# P16_Hi3531AV100_RGMII_I.net
KiCad netlist of a schematic drawn in Altium Designer
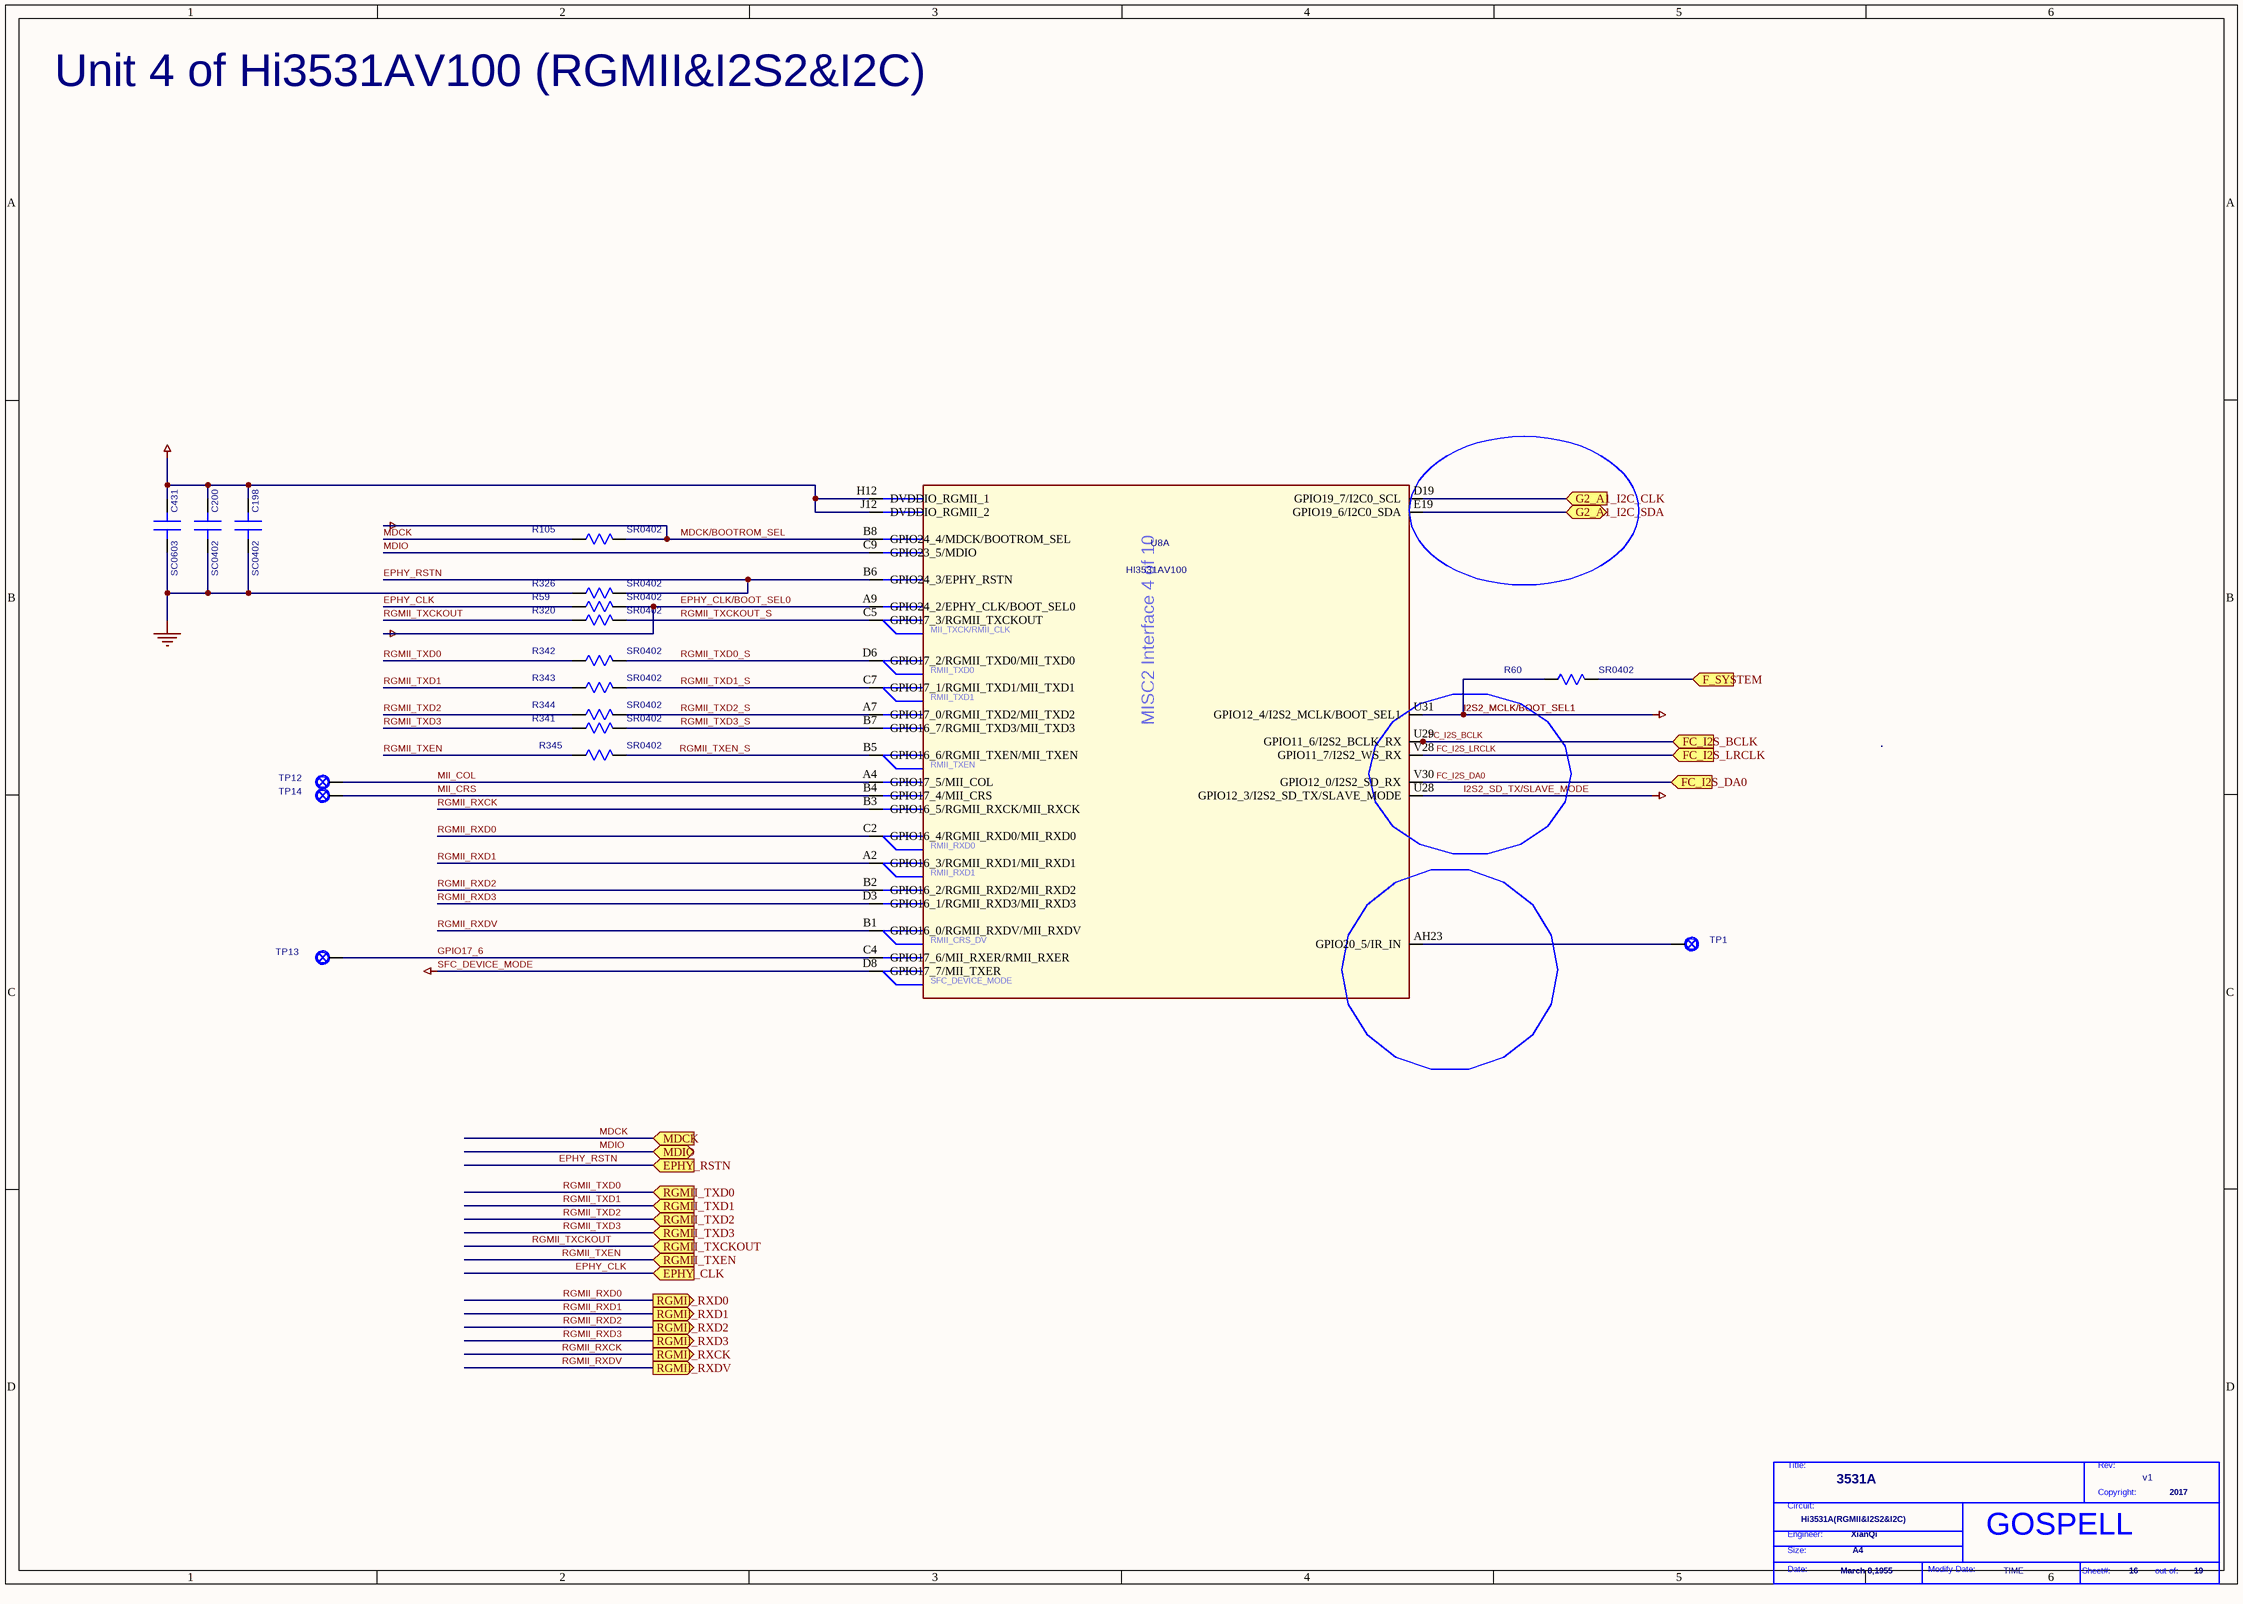
[diagram p0: P16 Hi3531AV100(RGMII&I.SchDoc]

(export (version "E")
  (design (tool "Eeschema 10.0.6"))
  (components
    (comp (ref "C198") (value "SC0402") (libsource (lib "*") (part "C_0_Dup2")))
    (comp (ref "C200") (value "SC0402") (libsource (lib "*") (part "C_0_Dup2")))
    (comp (ref "C431") (value "SC0603") (libsource (lib "*") (part "C_0_Dup2")))
    (comp (ref "R59") (value "SR0402") (libsource (lib "*") (part "R_1")))
    (comp (ref "R60") (value "SR0402") (libsource (lib "*") (part "R_1")))
    (comp (ref "R105") (value "SR0402") (libsource (lib "*") (part "R_1")))
    (comp (ref "R320") (value "SR0402") (libsource (lib "*") (part "R_1")))
    (comp (ref "R326") (value "SR0402") (libsource (lib "*") (part "R_1")))
    (comp (ref "R341") (value "SR0402") (libsource (lib "*") (part "R_1")))
    (comp (ref "R342") (value "SR0402") (libsource (lib "*") (part "R_1")))
    (comp (ref "R343") (value "SR0402") (libsource (lib "*") (part "R_1")))
    (comp (ref "R344") (value "SR0402") (libsource (lib "*") (part "R_1")))
    (comp (ref "R345") (value "SR0402") (libsource (lib "*") (part "R_1")))
    (comp (ref "TP1") (value "TP24-SMD") (libsource (lib "*") (part "TESTPOINT_0")))
    (comp (ref "TP12") (value "TP24-SMD") (libsource (lib "*") (part "TESTPOINT_0")))
    (comp (ref "TP13") (value "TP24-SMD") (libsource (lib "*") (part "TESTPOINT_0")))
    (comp (ref "TP14") (value "TP24-SMD") (libsource (lib "*") (part "TESTPOINT_0")))
    (comp (ref "U8")
      (value "BGA805-32-3333")
      (fields (field (name "DEVICE") "HI3531AV100"))
      (libsource (lib "*") (part "HI3531AV100_M2_17"))
    )
  )
  (nets
    (net (code "1") (name "/EPHY_CLK") (class "Default")
      (node (ref "R59") (pin "1") (pinfunction "A_1") (pintype "passive"))
    )
    (net (code "2") (name "/EPHY_RSTN") (class "Default")
      (node (ref "R326") (pin "2") (pinfunction "B_2") (pintype "passive"))
      (node (ref "U8") (pin "B6") (pinfunction "GPIO24_3/EPHY_RSTN_B6") (pintype "passive"))
    )
    (net (code "3") (name "/FC_I2S_BCLK") (class "Default")
      (node (ref "U8") (pin "U29") (pinfunction "GPIO11_6/I2S2_BCLK_RX_U29") (pintype "passive"))
    )
    (net (code "4") (name "/FC_I2S_DA0") (class "Default")
      (node (ref "U8") (pin "V30") (pinfunction "GPIO12_0/I2S2_SD_RX_V30") (pintype "passive"))
    )
    (net (code "5") (name "/FC_I2S_LRCLK") (class "Default")
      (node (ref "U8") (pin "V28") (pinfunction "GPIO11_7/I2S2_WS_RX_V28") (pintype "passive"))
    )
    (net (code "6") (name "/F_SYSTEM") (class "Default")
      (node (ref "R60") (pin "2") (pinfunction "B_2") (pintype "passive"))
    )
    (net (code "7") (name "/G2_A1_I2C_CLK") (class "Default")
      (node (ref "U8") (pin "D19") (pinfunction "GPIO19_7/I2C0_SCL_D19") (pintype "passive"))
    )
    (net (code "8") (name "/G2_A1_I2C_SDA") (class "Default")
      (node (ref "U8") (pin "E19") (pinfunction "GPIO19_6/I2C0_SDA_E19") (pintype "passive"))
    )
    (net (code "9") (name "/GPIO17_6") (class "Default")
      (node (ref "TP13") (pin "1") (pinfunction "1_1") (pintype "passive"))
      (node (ref "U8") (pin "C4") (pinfunction "GPIO17_6/MII_RXER/RMII_RXER_C4") (pintype "passive"))
    )
    (net (code "10") (name "/MDCK") (class "Default")
      (node (ref "R105") (pin "1") (pinfunction "A_1") (pintype "passive"))
    )
    (net (code "11") (name "/MDIO") (class "Default")
      (node (ref "U8") (pin "C9") (pinfunction "GPIO23_5/MDIO_C9") (pintype "passive"))
    )
    (net (code "12") (name "/MII_COL") (class "Default")
      (node (ref "TP12") (pin "1") (pinfunction "1_1") (pintype "passive"))
      (node (ref "U8") (pin "A4") (pinfunction "GPIO17_5/MII_COL_A4") (pintype "passive"))
    )
    (net (code "13") (name "/MII_CRS") (class "Default")
      (node (ref "TP14") (pin "1") (pinfunction "1_1") (pintype "passive"))
      (node (ref "U8") (pin "B4") (pinfunction "GPIO17_4/MII_CRS_B4") (pintype "passive"))
    )
    (net (code "14") (name "/RGMII_RXCK") (class "Default")
      (node (ref "U8") (pin "B3") (pinfunction "GPIO16_5/RGMII_RXCK/MII_RXCK_B3") (pintype "passive"))
    )
    (net (code "15") (name "/RGMII_RXD0") (class "Default")
      (node (ref "U8") (pin "C2") (pinfunction "GPIO16_4/RGMII_RXD0/MII_RXD0_C2") (pintype "passive"))
    )
    (net (code "16") (name "/RGMII_RXD1") (class "Default")
      (node (ref "U8") (pin "A2") (pinfunction "GPIO16_3/RGMII_RXD1/MII_RXD1_A2") (pintype "passive"))
    )
    (net (code "17") (name "/RGMII_RXD2") (class "Default")
      (node (ref "U8") (pin "B2") (pinfunction "GPIO16_2/RGMII_RXD2/MII_RXD2_B2") (pintype "passive"))
    )
    (net (code "18") (name "/RGMII_RXD3") (class "Default")
      (node (ref "U8") (pin "D3") (pinfunction "GPIO16_1/RGMII_RXD3/MII_RXD3_D3") (pintype "passive"))
    )
    (net (code "19") (name "/RGMII_RXDV") (class "Default")
      (node (ref "U8") (pin "B1") (pinfunction "GPIO16_0/RGMII_RXDV/MII_RXDV_B1") (pintype "passive"))
    )
    (net (code "20") (name "/RGMII_TXCKOUT") (class "Default")
      (node (ref "R320") (pin "1") (pinfunction "A_1") (pintype "passive"))
    )
    (net (code "21") (name "/RGMII_TXCKOUT_S") (class "Default")
      (node (ref "R320") (pin "2") (pinfunction "B_2") (pintype "passive"))
      (node (ref "U8") (pin "C5") (pinfunction "GPIO17_3/RGMII_TXCKOUT_C5") (pintype "passive"))
    )
    (net (code "22") (name "/RGMII_TXD0") (class "Default")
      (node (ref "R342") (pin "1") (pinfunction "A_1") (pintype "passive"))
    )
    (net (code "23") (name "/RGMII_TXD0_S") (class "Default")
      (node (ref "R342") (pin "2") (pinfunction "B_2") (pintype "passive"))
      (node (ref "U8") (pin "D6") (pinfunction "GPIO17_2/RGMII_TXD0/MII_TXD0_D6") (pintype "passive"))
    )
    (net (code "24") (name "/RGMII_TXD1") (class "Default")
      (node (ref "R343") (pin "1") (pinfunction "A_1") (pintype "passive"))
    )
    (net (code "25") (name "/RGMII_TXD1_S") (class "Default")
      (node (ref "R343") (pin "2") (pinfunction "B_2") (pintype "passive"))
      (node (ref "U8") (pin "C7") (pinfunction "GPIO17_1/RGMII_TXD1/MII_TXD1_C7") (pintype "passive"))
    )
    (net (code "26") (name "/RGMII_TXD2") (class "Default")
      (node (ref "R344") (pin "1") (pinfunction "A_1") (pintype "passive"))
    )
    (net (code "27") (name "/RGMII_TXD2_S") (class "Default")
      (node (ref "R344") (pin "2") (pinfunction "B_2") (pintype "passive"))
      (node (ref "U8") (pin "A7") (pinfunction "GPIO17_0/RGMII_TXD2/MII_TXD2_A7") (pintype "passive"))
    )
    (net (code "28") (name "/RGMII_TXD3") (class "Default")
      (node (ref "R341") (pin "1") (pinfunction "A_1") (pintype "passive"))
    )
    (net (code "29") (name "/RGMII_TXD3_S") (class "Default")
      (node (ref "R341") (pin "2") (pinfunction "B_2") (pintype "passive"))
      (node (ref "U8") (pin "B7") (pinfunction "GPIO16_7/RGMII_TXD3/MII_TXD3_B7") (pintype "passive"))
    )
    (net (code "30") (name "/RGMII_TXEN") (class "Default")
      (node (ref "R345") (pin "1") (pinfunction "A_1") (pintype "passive"))
    )
    (net (code "31") (name "/RGMII_TXEN_S") (class "Default")
      (node (ref "R345") (pin "2") (pinfunction "B_2") (pintype "passive"))
      (node (ref "U8") (pin "B5") (pinfunction "GPIO16_6/RGMII_TXEN/MII_TXEN_B5") (pintype "passive"))
    )
    (net (code "32") (name "3V3") (class "Default")
      (node (ref "C198") (pin "1") (pinfunction "A_1") (pintype "passive"))
      (node (ref "C200") (pin "1") (pinfunction "A_1") (pintype "passive"))
      (node (ref "C431") (pin "1") (pinfunction "A_1") (pintype "passive"))
      (node (ref "U8") (pin "H12") (pinfunction "DVDDIO_RGMII_1_H12") (pintype "passive"))
      (node (ref "U8") (pin "J12") (pinfunction "DVDDIO_RGMII_2_J12") (pintype "passive"))
    )
    (net (code "33") (name "EPHY_CLK{slash}BOOT_SEL0") (class "Default")
      (node (ref "R59") (pin "2") (pinfunction "B_2") (pintype "passive"))
      (node (ref "U8") (pin "A9") (pinfunction "GPIO24_2/EPHY_CLK/BOOT_SEL0_A9") (pintype "passive"))
    )
    (net (code "34") (name "GND") (class "Default")
      (node (ref "C198") (pin "2") (pinfunction "B_2") (pintype "passive"))
      (node (ref "C200") (pin "2") (pinfunction "B_2") (pintype "passive"))
      (node (ref "C431") (pin "2") (pinfunction "B_2") (pintype "passive"))
      (node (ref "R326") (pin "1") (pinfunction "A_1") (pintype "passive"))
    )
    (net (code "35") (name "I2S2_MCLK{slash}BOOT_SEL1") (class "Default")
      (node (ref "R60") (pin "1") (pinfunction "A_1") (pintype "passive"))
      (node (ref "U8") (pin "U31") (pinfunction "GPIO12_4/I2S2_MCLK/BOOT_SEL1_U31") (pintype "passive"))
    )
    (net (code "36") (name "I2S2_SD_TX{slash}SLAVE_MODE") (class "Default")
      (node (ref "U8") (pin "U28") (pinfunction "GPIO12_3/I2S2_SD_TX/SLAVE_MODE_U28") (pintype "passive"))
    )
    (net (code "37") (name "MDCK{slash}BOOTROM_SEL") (class "Default")
      (node (ref "R105") (pin "2") (pinfunction "B_2") (pintype "passive"))
      (node (ref "U8") (pin "B8") (pinfunction "GPIO24_4/MDCK/BOOTROM_SEL_B8") (pintype "passive"))
    )
    (net (code "38") (name "Net-(U8A-GPIO20_5{slash}IR_IN)") (class "Default")
      (node (ref "TP1") (pin "1") (pinfunction "1_1") (pintype "passive"))
      (node (ref "U8") (pin "AH23") (pinfunction "GPIO20_5/IR_IN_AH23") (pintype "passive"))
    )
    (net (code "39") (name "SFC_DEVICE_MODE") (class "Default")
      (node (ref "U8") (pin "D8") (pinfunction "GPIO17_7/MII_TXER_D8") (pintype "passive"))
    )
  )
)
